# 2008_SablierElectronique_MosfetConnectio.net
KiCad netlist of a schematic drawn in Altium Designer
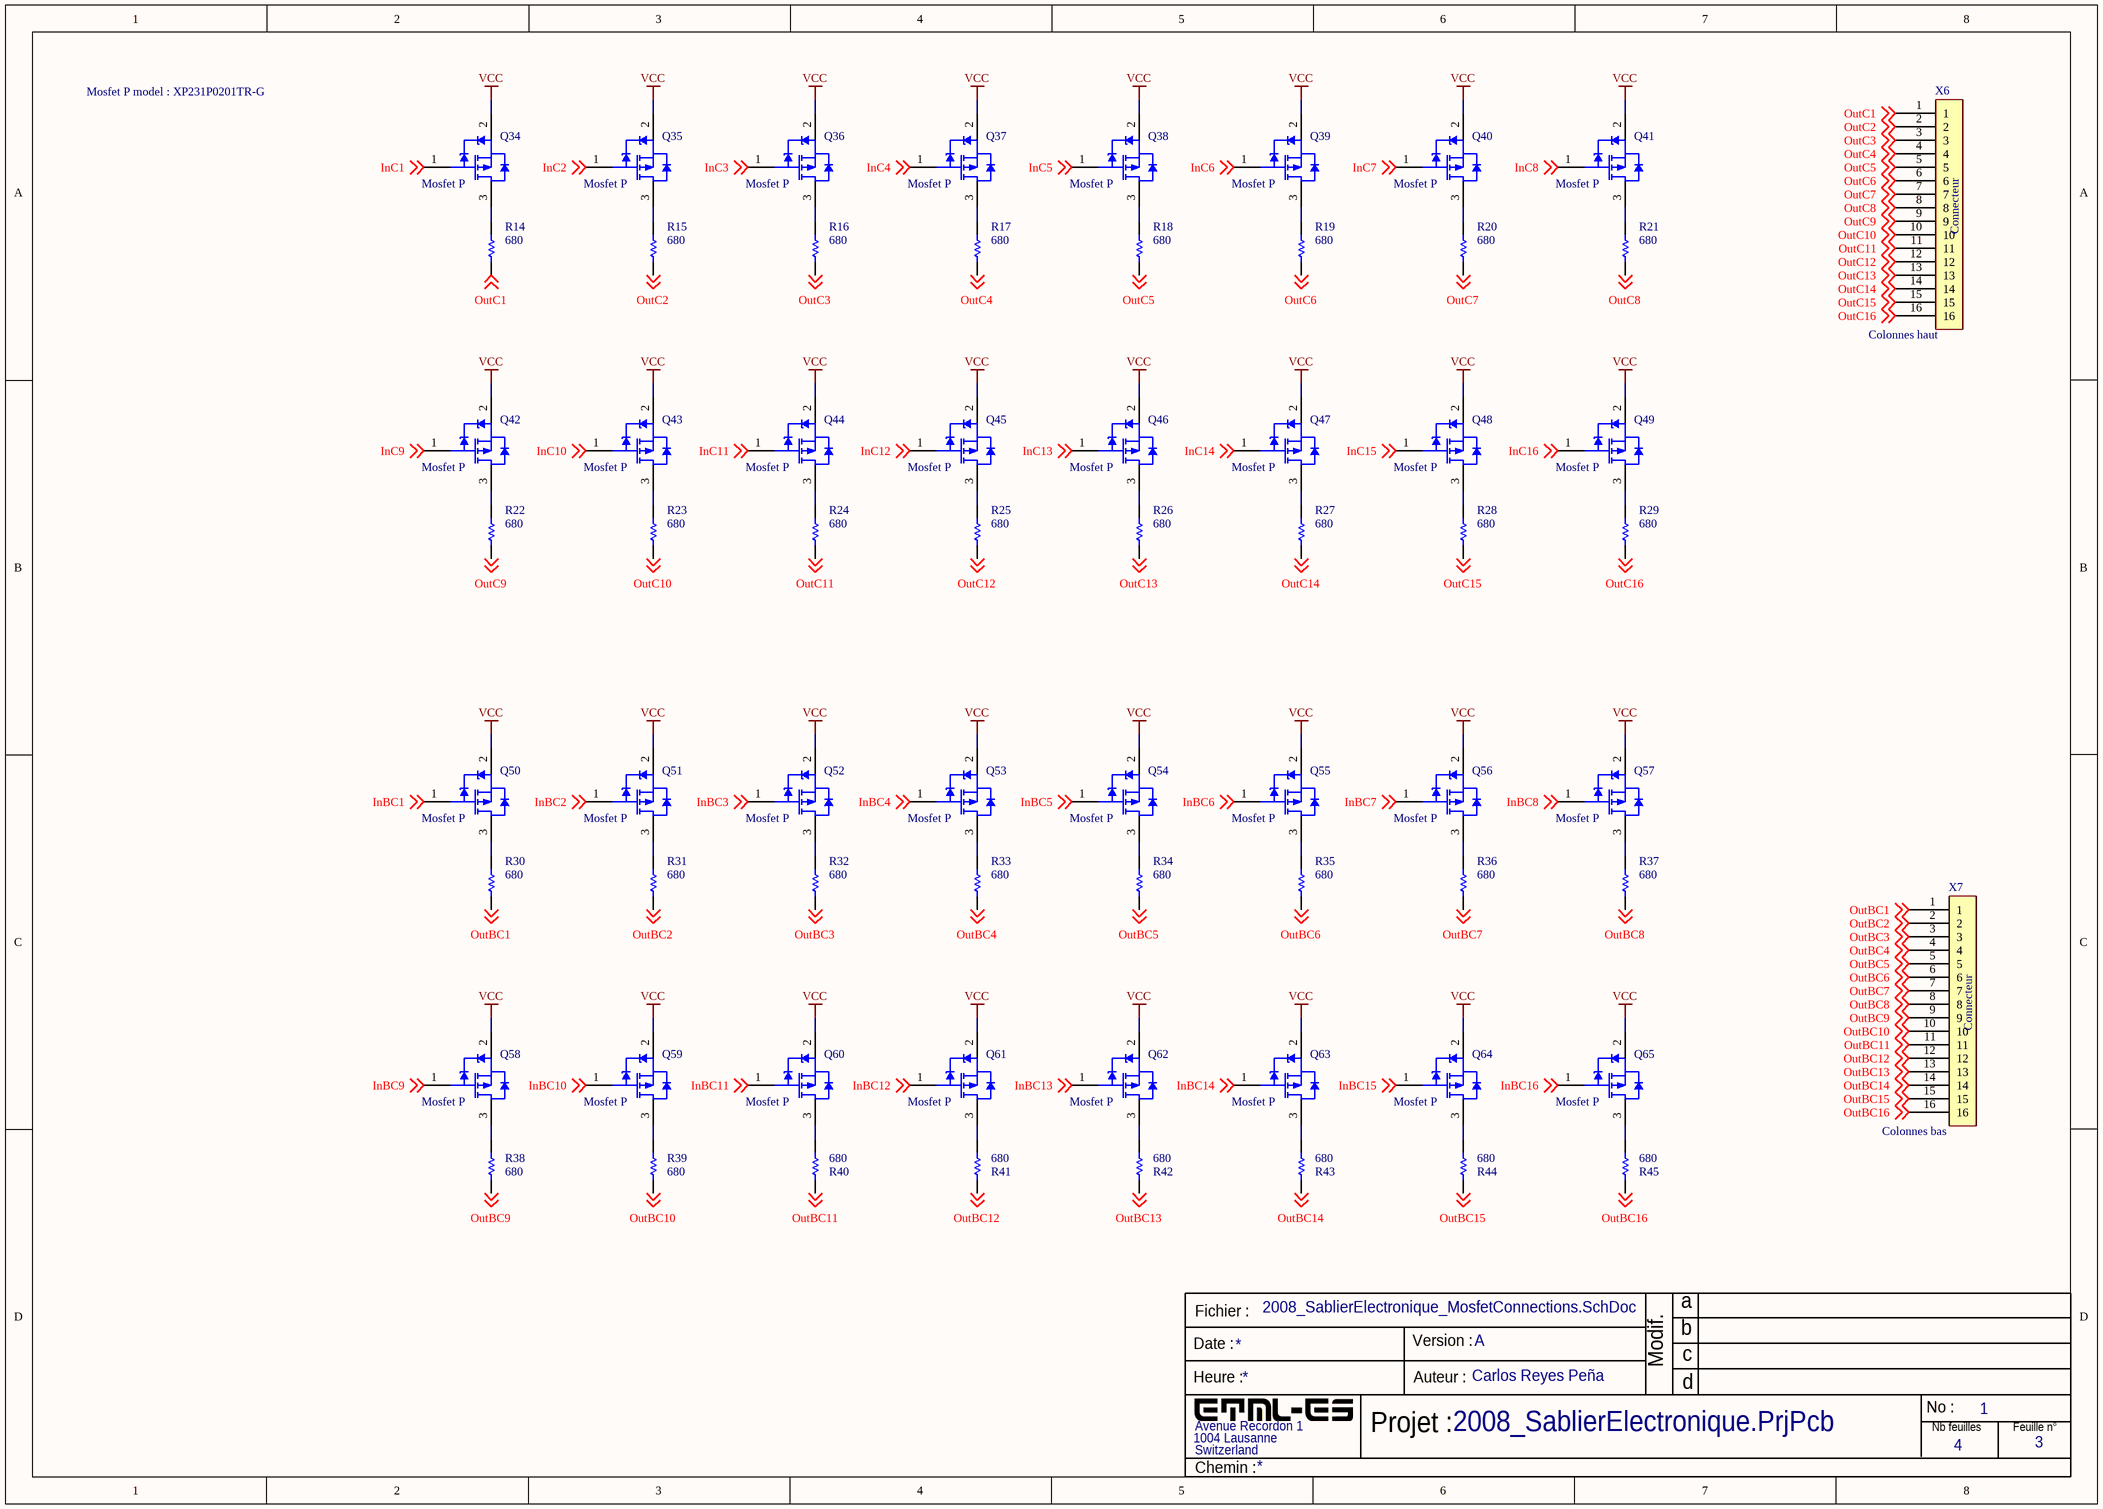
[diagram p0: 2008_SablierElectronique_MosfetConnections.SchDoc]

(export (version "E")
  (design (tool "Eeschema 10.0.6"))
  (components
    (comp (ref "Q34")
      (value "Mosfet P")
      (footprint "FAIR-SOT23-3_V")
      (libsource (lib "2008_SablierElectronique_SCHLIB") (part "Mosfet P"))
    )
    (comp (ref "Q35")
      (value "Mosfet P")
      (footprint "FAIR-SOT23-3_V")
      (libsource (lib "2008_SablierElectronique_SCHLIB") (part "Mosfet P"))
    )
    (comp (ref "Q36")
      (value "Mosfet P")
      (footprint "FAIR-SOT23-3_V")
      (libsource (lib "2008_SablierElectronique_SCHLIB") (part "Mosfet P"))
    )
    (comp (ref "Q37")
      (value "Mosfet P")
      (footprint "FAIR-SOT23-3_V")
      (libsource (lib "2008_SablierElectronique_SCHLIB") (part "Mosfet P"))
    )
    (comp (ref "Q38")
      (value "Mosfet P")
      (footprint "FAIR-SOT23-3_V")
      (libsource (lib "2008_SablierElectronique_SCHLIB") (part "Mosfet P"))
    )
    (comp (ref "Q39")
      (value "Mosfet P")
      (footprint "FAIR-SOT23-3_V")
      (libsource (lib "2008_SablierElectronique_SCHLIB") (part "Mosfet P"))
    )
    (comp (ref "Q40")
      (value "Mosfet P")
      (footprint "FAIR-SOT23-3_V")
      (libsource (lib "2008_SablierElectronique_SCHLIB") (part "Mosfet P"))
    )
    (comp (ref "Q41")
      (value "Mosfet P")
      (footprint "FAIR-SOT23-3_V")
      (libsource (lib "2008_SablierElectronique_SCHLIB") (part "Mosfet P"))
    )
    (comp (ref "Q42")
      (value "Mosfet P")
      (footprint "FAIR-SOT23-3_V")
      (libsource (lib "2008_SablierElectronique_SCHLIB") (part "Mosfet P"))
    )
    (comp (ref "Q43")
      (value "Mosfet P")
      (footprint "FAIR-SOT23-3_V")
      (libsource (lib "2008_SablierElectronique_SCHLIB") (part "Mosfet P"))
    )
    (comp (ref "Q44")
      (value "Mosfet P")
      (footprint "FAIR-SOT23-3_V")
      (libsource (lib "2008_SablierElectronique_SCHLIB") (part "Mosfet P"))
    )
    (comp (ref "Q45")
      (value "Mosfet P")
      (footprint "FAIR-SOT23-3_V")
      (libsource (lib "2008_SablierElectronique_SCHLIB") (part "Mosfet P"))
    )
    (comp (ref "Q46")
      (value "Mosfet P")
      (footprint "FAIR-SOT23-3_V")
      (libsource (lib "2008_SablierElectronique_SCHLIB") (part "Mosfet P"))
    )
    (comp (ref "Q47")
      (value "Mosfet P")
      (footprint "FAIR-SOT23-3_V")
      (libsource (lib "2008_SablierElectronique_SCHLIB") (part "Mosfet P"))
    )
    (comp (ref "Q48")
      (value "Mosfet P")
      (footprint "FAIR-SOT23-3_V")
      (libsource (lib "2008_SablierElectronique_SCHLIB") (part "Mosfet P"))
    )
    (comp (ref "Q49")
      (value "Mosfet P")
      (footprint "FAIR-SOT23-3_V")
      (libsource (lib "2008_SablierElectronique_SCHLIB") (part "Mosfet P"))
    )
    (comp (ref "Q50")
      (value "Mosfet P")
      (footprint "FAIR-SOT23-3_V")
      (libsource (lib "2008_SablierElectronique_SCHLIB") (part "Mosfet P"))
    )
    (comp (ref "Q51")
      (value "Mosfet P")
      (footprint "FAIR-SOT23-3_V")
      (libsource (lib "2008_SablierElectronique_SCHLIB") (part "Mosfet P"))
    )
    (comp (ref "Q52")
      (value "Mosfet P")
      (footprint "FAIR-SOT23-3_V")
      (libsource (lib "2008_SablierElectronique_SCHLIB") (part "Mosfet P"))
    )
    (comp (ref "Q53")
      (value "Mosfet P")
      (footprint "FAIR-SOT23-3_V")
      (libsource (lib "2008_SablierElectronique_SCHLIB") (part "Mosfet P"))
    )
    (comp (ref "Q54")
      (value "Mosfet P")
      (footprint "FAIR-SOT23-3_V")
      (libsource (lib "2008_SablierElectronique_SCHLIB") (part "Mosfet P"))
    )
    (comp (ref "Q55")
      (value "Mosfet P")
      (footprint "FAIR-SOT23-3_V")
      (libsource (lib "2008_SablierElectronique_SCHLIB") (part "Mosfet P"))
    )
    (comp (ref "Q56")
      (value "Mosfet P")
      (footprint "FAIR-SOT23-3_V")
      (libsource (lib "2008_SablierElectronique_SCHLIB") (part "Mosfet P"))
    )
    (comp (ref "Q57")
      (value "Mosfet P")
      (footprint "FAIR-SOT23-3_V")
      (libsource (lib "2008_SablierElectronique_SCHLIB") (part "Mosfet P"))
    )
    (comp (ref "Q58")
      (value "Mosfet P")
      (footprint "FAIR-SOT23-3_V")
      (libsource (lib "2008_SablierElectronique_SCHLIB") (part "Mosfet P"))
    )
    (comp (ref "Q59")
      (value "Mosfet P")
      (footprint "FAIR-SOT23-3_V")
      (libsource (lib "2008_SablierElectronique_SCHLIB") (part "Mosfet P"))
    )
    (comp (ref "Q60")
      (value "Mosfet P")
      (footprint "FAIR-SOT23-3_V")
      (libsource (lib "2008_SablierElectronique_SCHLIB") (part "Mosfet P"))
    )
    (comp (ref "Q61")
      (value "Mosfet P")
      (footprint "FAIR-SOT23-3_V")
      (libsource (lib "2008_SablierElectronique_SCHLIB") (part "Mosfet P"))
    )
    (comp (ref "Q62")
      (value "Mosfet P")
      (footprint "FAIR-SOT23-3_V")
      (libsource (lib "2008_SablierElectronique_SCHLIB") (part "Mosfet P"))
    )
    (comp (ref "Q63")
      (value "Mosfet P")
      (footprint "FAIR-SOT23-3_V")
      (libsource (lib "2008_SablierElectronique_SCHLIB") (part "Mosfet P"))
    )
    (comp (ref "Q64")
      (value "Mosfet P")
      (footprint "FAIR-SOT23-3_V")
      (libsource (lib "2008_SablierElectronique_SCHLIB") (part "Mosfet P"))
    )
    (comp (ref "Q65")
      (value "Mosfet P")
      (footprint "FAIR-SOT23-3_V")
      (libsource (lib "2008_SablierElectronique_SCHLIB") (part "Mosfet P"))
    )
    (comp (ref "R14")
      (value "680")
      (footprint "RESC0805(2012)_L")
      (libsource (lib "2008_SablierElectronique_SCHLIB") (part "RES"))
    )
    (comp (ref "R15")
      (value "680")
      (footprint "RESC0805(2012)_L")
      (libsource (lib "2008_SablierElectronique_SCHLIB") (part "RES"))
    )
    (comp (ref "R16")
      (value "680")
      (footprint "RESC0805(2012)_L")
      (libsource (lib "2008_SablierElectronique_SCHLIB") (part "RES"))
    )
    (comp (ref "R17")
      (value "680")
      (footprint "RESC0805(2012)_L")
      (libsource (lib "2008_SablierElectronique_SCHLIB") (part "RES"))
    )
    (comp (ref "R18")
      (value "680")
      (footprint "RESC0805(2012)_L")
      (libsource (lib "2008_SablierElectronique_SCHLIB") (part "RES"))
    )
    (comp (ref "R19")
      (value "680")
      (footprint "RESC0805(2012)_L")
      (libsource (lib "2008_SablierElectronique_SCHLIB") (part "RES"))
    )
    (comp (ref "R20")
      (value "680")
      (footprint "RESC0805(2012)_L")
      (libsource (lib "2008_SablierElectronique_SCHLIB") (part "RES"))
    )
    (comp (ref "R21")
      (value "680")
      (footprint "RESC0805(2012)_L")
      (libsource (lib "2008_SablierElectronique_SCHLIB") (part "RES"))
    )
    (comp (ref "R22")
      (value "680")
      (footprint "RESC0805(2012)_L")
      (libsource (lib "2008_SablierElectronique_SCHLIB") (part "RES"))
    )
    (comp (ref "R23")
      (value "680")
      (footprint "RESC0805(2012)_L")
      (libsource (lib "2008_SablierElectronique_SCHLIB") (part "RES"))
    )
    (comp (ref "R24")
      (value "680")
      (footprint "RESC0805(2012)_L")
      (libsource (lib "2008_SablierElectronique_SCHLIB") (part "RES"))
    )
    (comp (ref "R25")
      (value "680")
      (footprint "RESC0805(2012)_L")
      (libsource (lib "2008_SablierElectronique_SCHLIB") (part "RES"))
    )
    (comp (ref "R26")
      (value "680")
      (footprint "RESC0805(2012)_L")
      (libsource (lib "2008_SablierElectronique_SCHLIB") (part "RES"))
    )
    (comp (ref "R27")
      (value "680")
      (footprint "RESC0805(2012)_L")
      (libsource (lib "2008_SablierElectronique_SCHLIB") (part "RES"))
    )
    (comp (ref "R28")
      (value "680")
      (footprint "RESC0805(2012)_L")
      (libsource (lib "2008_SablierElectronique_SCHLIB") (part "RES"))
    )
    (comp (ref "R29")
      (value "680")
      (footprint "RESC0805(2012)_L")
      (libsource (lib "2008_SablierElectronique_SCHLIB") (part "RES"))
    )
    (comp (ref "R30")
      (value "680")
      (footprint "RESC0805(2012)_L")
      (libsource (lib "2008_SablierElectronique_SCHLIB") (part "RES"))
    )
    (comp (ref "R31")
      (value "680")
      (footprint "RESC0805(2012)_L")
      (libsource (lib "2008_SablierElectronique_SCHLIB") (part "RES"))
    )
    (comp (ref "R32")
      (value "680")
      (footprint "RESC0805(2012)_L")
      (libsource (lib "2008_SablierElectronique_SCHLIB") (part "RES"))
    )
    (comp (ref "R33")
      (value "680")
      (footprint "RESC0805(2012)_L")
      (libsource (lib "2008_SablierElectronique_SCHLIB") (part "RES"))
    )
    (comp (ref "R34")
      (value "680")
      (footprint "RESC0805(2012)_L")
      (libsource (lib "2008_SablierElectronique_SCHLIB") (part "RES"))
    )
    (comp (ref "R35")
      (value "680")
      (footprint "RESC0805(2012)_L")
      (libsource (lib "2008_SablierElectronique_SCHLIB") (part "RES"))
    )
    (comp (ref "R36")
      (value "680")
      (footprint "RESC0805(2012)_L")
      (libsource (lib "2008_SablierElectronique_SCHLIB") (part "RES"))
    )
    (comp (ref "R37")
      (value "680")
      (footprint "RESC0805(2012)_L")
      (libsource (lib "2008_SablierElectronique_SCHLIB") (part "RES"))
    )
    (comp (ref "R38")
      (value "680")
      (footprint "RESC0805(2012)_L")
      (libsource (lib "2008_SablierElectronique_SCHLIB") (part "RES"))
    )
    (comp (ref "R39")
      (value "680")
      (footprint "RESC0805(2012)_L")
      (libsource (lib "2008_SablierElectronique_SCHLIB") (part "RES"))
    )
    (comp (ref "R40")
      (value "680")
      (footprint "RESC0805(2012)_L")
      (libsource (lib "2008_SablierElectronique_SCHLIB") (part "RES"))
    )
    (comp (ref "R41")
      (value "680")
      (footprint "RESC0805(2012)_L")
      (libsource (lib "2008_SablierElectronique_SCHLIB") (part "RES"))
    )
    (comp (ref "R42")
      (value "680")
      (footprint "RESC0805(2012)_L")
      (libsource (lib "2008_SablierElectronique_SCHLIB") (part "RES"))
    )
    (comp (ref "R43")
      (value "680")
      (footprint "RESC0805(2012)_L")
      (libsource (lib "2008_SablierElectronique_SCHLIB") (part "RES"))
    )
    (comp (ref "R44")
      (value "680")
      (footprint "RESC0805(2012)_L")
      (libsource (lib "2008_SablierElectronique_SCHLIB") (part "RES"))
    )
    (comp (ref "R45")
      (value "680")
      (footprint "RESC0805(2012)_L")
      (libsource (lib "2008_SablierElectronique_SCHLIB") (part "RES"))
    )
    (comp (ref "X6")
      (value "Colonnes haut")
      (footprint "CON8x8(edited)")
      (libsource (lib "2008_SablierElectronique_SCHLIB") (part "Mâle DIN 8 x 8"))
    )
    (comp (ref "X7")
      (value "Colonnes bas")
      (footprint "CON8x8(edited)")
      (libsource (lib "2008_SablierElectronique_SCHLIB") (part "Mâle DIN 8 x 8"))
    )
  )
  (nets
    (net (code "1") (name "InBC1") (class "Default")
      (node (ref "Q50") (pin "1") (pinfunction "G_1") (pintype "passive"))
    )
    (net (code "2") (name "InBC2") (class "Default")
      (node (ref "Q51") (pin "1") (pinfunction "G_1") (pintype "passive"))
    )
    (net (code "3") (name "InBC3") (class "Default")
      (node (ref "Q52") (pin "1") (pinfunction "G_1") (pintype "passive"))
    )
    (net (code "4") (name "InBC4") (class "Default")
      (node (ref "Q53") (pin "1") (pinfunction "G_1") (pintype "passive"))
    )
    (net (code "5") (name "InBC5") (class "Default")
      (node (ref "Q54") (pin "1") (pinfunction "G_1") (pintype "passive"))
    )
    (net (code "6") (name "InBC6") (class "Default")
      (node (ref "Q55") (pin "1") (pinfunction "G_1") (pintype "passive"))
    )
    (net (code "7") (name "InBC7") (class "Default")
      (node (ref "Q56") (pin "1") (pinfunction "G_1") (pintype "passive"))
    )
    (net (code "8") (name "InBC8") (class "Default")
      (node (ref "Q57") (pin "1") (pinfunction "G_1") (pintype "passive"))
    )
    (net (code "9") (name "InBC9") (class "Default")
      (node (ref "Q58") (pin "1") (pinfunction "G_1") (pintype "passive"))
    )
    (net (code "10") (name "InBC10") (class "Default")
      (node (ref "Q59") (pin "1") (pinfunction "G_1") (pintype "passive"))
    )
    (net (code "11") (name "InBC11") (class "Default")
      (node (ref "Q60") (pin "1") (pinfunction "G_1") (pintype "passive"))
    )
    (net (code "12") (name "InBC12") (class "Default")
      (node (ref "Q61") (pin "1") (pinfunction "G_1") (pintype "passive"))
    )
    (net (code "13") (name "InBC13") (class "Default")
      (node (ref "Q62") (pin "1") (pinfunction "G_1") (pintype "passive"))
    )
    (net (code "14") (name "InBC14") (class "Default")
      (node (ref "Q63") (pin "1") (pinfunction "G_1") (pintype "passive"))
    )
    (net (code "15") (name "InBC15") (class "Default")
      (node (ref "Q64") (pin "1") (pinfunction "G_1") (pintype "passive"))
    )
    (net (code "16") (name "InBC16") (class "Default")
      (node (ref "Q65") (pin "1") (pinfunction "G_1") (pintype "passive"))
    )
    (net (code "17") (name "InC1") (class "Default")
      (node (ref "Q34") (pin "1") (pinfunction "G_1") (pintype "passive"))
    )
    (net (code "18") (name "InC2") (class "Default")
      (node (ref "Q35") (pin "1") (pinfunction "G_1") (pintype "passive"))
    )
    (net (code "19") (name "InC3") (class "Default")
      (node (ref "Q36") (pin "1") (pinfunction "G_1") (pintype "passive"))
    )
    (net (code "20") (name "InC4") (class "Default")
      (node (ref "Q37") (pin "1") (pinfunction "G_1") (pintype "passive"))
    )
    (net (code "21") (name "InC5") (class "Default")
      (node (ref "Q38") (pin "1") (pinfunction "G_1") (pintype "passive"))
    )
    (net (code "22") (name "InC6") (class "Default")
      (node (ref "Q39") (pin "1") (pinfunction "G_1") (pintype "passive"))
    )
    (net (code "23") (name "InC7") (class "Default")
      (node (ref "Q40") (pin "1") (pinfunction "G_1") (pintype "passive"))
    )
    (net (code "24") (name "InC8") (class "Default")
      (node (ref "Q41") (pin "1") (pinfunction "G_1") (pintype "passive"))
    )
    (net (code "25") (name "InC9") (class "Default")
      (node (ref "Q42") (pin "1") (pinfunction "G_1") (pintype "passive"))
    )
    (net (code "26") (name "InC10") (class "Default")
      (node (ref "Q43") (pin "1") (pinfunction "G_1") (pintype "passive"))
    )
    (net (code "27") (name "InC11") (class "Default")
      (node (ref "Q44") (pin "1") (pinfunction "G_1") (pintype "passive"))
    )
    (net (code "28") (name "InC12") (class "Default")
      (node (ref "Q45") (pin "1") (pinfunction "G_1") (pintype "passive"))
    )
    (net (code "29") (name "InC13") (class "Default")
      (node (ref "Q46") (pin "1") (pinfunction "G_1") (pintype "passive"))
    )
    (net (code "30") (name "InC14") (class "Default")
      (node (ref "Q47") (pin "1") (pinfunction "G_1") (pintype "passive"))
    )
    (net (code "31") (name "InC15") (class "Default")
      (node (ref "Q48") (pin "1") (pinfunction "G_1") (pintype "passive"))
    )
    (net (code "32") (name "InC16") (class "Default")
      (node (ref "Q49") (pin "1") (pinfunction "G_1") (pintype "passive"))
    )
    (net (code "33") (name "Net-(Q34-D)") (class "Default")
      (node (ref "Q34") (pin "3") (pinfunction "D_3") (pintype "passive"))
      (node (ref "R14") (pin "2") (pinfunction "2_2") (pintype "passive"))
    )
    (net (code "34") (name "Net-(Q35-D)") (class "Default")
      (node (ref "Q35") (pin "3") (pinfunction "D_3") (pintype "passive"))
      (node (ref "R15") (pin "2") (pinfunction "2_2") (pintype "passive"))
    )
    (net (code "35") (name "Net-(Q36-D)") (class "Default")
      (node (ref "Q36") (pin "3") (pinfunction "D_3") (pintype "passive"))
      (node (ref "R16") (pin "2") (pinfunction "2_2") (pintype "passive"))
    )
    (net (code "36") (name "Net-(Q37-D)") (class "Default")
      (node (ref "Q37") (pin "3") (pinfunction "D_3") (pintype "passive"))
      (node (ref "R17") (pin "2") (pinfunction "2_2") (pintype "passive"))
    )
    (net (code "37") (name "Net-(Q38-D)") (class "Default")
      (node (ref "Q38") (pin "3") (pinfunction "D_3") (pintype "passive"))
      (node (ref "R18") (pin "2") (pinfunction "2_2") (pintype "passive"))
    )
    (net (code "38") (name "Net-(Q39-D)") (class "Default")
      (node (ref "Q39") (pin "3") (pinfunction "D_3") (pintype "passive"))
      (node (ref "R19") (pin "2") (pinfunction "2_2") (pintype "passive"))
    )
    (net (code "39") (name "Net-(Q40-D)") (class "Default")
      (node (ref "Q40") (pin "3") (pinfunction "D_3") (pintype "passive"))
      (node (ref "R20") (pin "2") (pinfunction "2_2") (pintype "passive"))
    )
    (net (code "40") (name "Net-(Q41-D)") (class "Default")
      (node (ref "Q41") (pin "3") (pinfunction "D_3") (pintype "passive"))
      (node (ref "R21") (pin "2") (pinfunction "2_2") (pintype "passive"))
    )
    (net (code "41") (name "Net-(Q42-D)") (class "Default")
      (node (ref "Q42") (pin "3") (pinfunction "D_3") (pintype "passive"))
      (node (ref "R22") (pin "2") (pinfunction "2_2") (pintype "passive"))
    )
    (net (code "42") (name "Net-(Q43-D)") (class "Default")
      (node (ref "Q43") (pin "3") (pinfunction "D_3") (pintype "passive"))
      (node (ref "R23") (pin "2") (pinfunction "2_2") (pintype "passive"))
    )
    (net (code "43") (name "Net-(Q44-D)") (class "Default")
      (node (ref "Q44") (pin "3") (pinfunction "D_3") (pintype "passive"))
      (node (ref "R24") (pin "2") (pinfunction "2_2") (pintype "passive"))
    )
    (net (code "44") (name "Net-(Q45-D)") (class "Default")
      (node (ref "Q45") (pin "3") (pinfunction "D_3") (pintype "passive"))
      (node (ref "R25") (pin "2") (pinfunction "2_2") (pintype "passive"))
    )
    (net (code "45") (name "Net-(Q46-D)") (class "Default")
      (node (ref "Q46") (pin "3") (pinfunction "D_3") (pintype "passive"))
      (node (ref "R26") (pin "2") (pinfunction "2_2") (pintype "passive"))
    )
    (net (code "46") (name "Net-(Q47-D)") (class "Default")
      (node (ref "Q47") (pin "3") (pinfunction "D_3") (pintype "passive"))
      (node (ref "R27") (pin "2") (pinfunction "2_2") (pintype "passive"))
    )
    (net (code "47") (name "Net-(Q48-D)") (class "Default")
      (node (ref "Q48") (pin "3") (pinfunction "D_3") (pintype "passive"))
      (node (ref "R28") (pin "2") (pinfunction "2_2") (pintype "passive"))
    )
    (net (code "48") (name "Net-(Q49-D)") (class "Default")
      (node (ref "Q49") (pin "3") (pinfunction "D_3") (pintype "passive"))
      (node (ref "R29") (pin "2") (pinfunction "2_2") (pintype "passive"))
    )
    (net (code "49") (name "Net-(Q50-D)") (class "Default")
      (node (ref "Q50") (pin "3") (pinfunction "D_3") (pintype "passive"))
      (node (ref "R30") (pin "2") (pinfunction "2_2") (pintype "passive"))
    )
    (net (code "50") (name "Net-(Q51-D)") (class "Default")
      (node (ref "Q51") (pin "3") (pinfunction "D_3") (pintype "passive"))
      (node (ref "R31") (pin "2") (pinfunction "2_2") (pintype "passive"))
    )
    (net (code "51") (name "Net-(Q52-D)") (class "Default")
      (node (ref "Q52") (pin "3") (pinfunction "D_3") (pintype "passive"))
      (node (ref "R32") (pin "2") (pinfunction "2_2") (pintype "passive"))
    )
    (net (code "52") (name "Net-(Q53-D)") (class "Default")
      (node (ref "Q53") (pin "3") (pinfunction "D_3") (pintype "passive"))
      (node (ref "R33") (pin "2") (pinfunction "2_2") (pintype "passive"))
    )
    (net (code "53") (name "Net-(Q54-D)") (class "Default")
      (node (ref "Q54") (pin "3") (pinfunction "D_3") (pintype "passive"))
      (node (ref "R34") (pin "2") (pinfunction "2_2") (pintype "passive"))
    )
    (net (code "54") (name "Net-(Q55-D)") (class "Default")
      (node (ref "Q55") (pin "3") (pinfunction "D_3") (pintype "passive"))
      (node (ref "R35") (pin "2") (pinfunction "2_2") (pintype "passive"))
    )
    (net (code "55") (name "Net-(Q56-D)") (class "Default")
      (node (ref "Q56") (pin "3") (pinfunction "D_3") (pintype "passive"))
      (node (ref "R36") (pin "2") (pinfunction "2_2") (pintype "passive"))
    )
    (net (code "56") (name "Net-(Q57-D)") (class "Default")
      (node (ref "Q57") (pin "3") (pinfunction "D_3") (pintype "passive"))
      (node (ref "R37") (pin "2") (pinfunction "2_2") (pintype "passive"))
    )
    (net (code "57") (name "Net-(Q58-D)") (class "Default")
      (node (ref "Q58") (pin "3") (pinfunction "D_3") (pintype "passive"))
      (node (ref "R38") (pin "2") (pinfunction "2_2") (pintype "passive"))
    )
    (net (code "58") (name "Net-(Q59-D)") (class "Default")
      (node (ref "Q59") (pin "3") (pinfunction "D_3") (pintype "passive"))
      (node (ref "R39") (pin "2") (pinfunction "2_2") (pintype "passive"))
    )
    (net (code "59") (name "Net-(Q60-D)") (class "Default")
      (node (ref "Q60") (pin "3") (pinfunction "D_3") (pintype "passive"))
      (node (ref "R40") (pin "2") (pinfunction "2_2") (pintype "passive"))
    )
    (net (code "60") (name "Net-(Q61-D)") (class "Default")
      (node (ref "Q61") (pin "3") (pinfunction "D_3") (pintype "passive"))
      (node (ref "R41") (pin "2") (pinfunction "2_2") (pintype "passive"))
    )
    (net (code "61") (name "Net-(Q62-D)") (class "Default")
      (node (ref "Q62") (pin "3") (pinfunction "D_3") (pintype "passive"))
      (node (ref "R42") (pin "2") (pinfunction "2_2") (pintype "passive"))
    )
    (net (code "62") (name "Net-(Q63-D)") (class "Default")
      (node (ref "Q63") (pin "3") (pinfunction "D_3") (pintype "passive"))
      (node (ref "R43") (pin "2") (pinfunction "2_2") (pintype "passive"))
    )
    (net (code "63") (name "Net-(Q64-D)") (class "Default")
      (node (ref "Q64") (pin "3") (pinfunction "D_3") (pintype "passive"))
      (node (ref "R44") (pin "2") (pinfunction "2_2") (pintype "passive"))
    )
    (net (code "64") (name "Net-(Q65-D)") (class "Default")
      (node (ref "Q65") (pin "3") (pinfunction "D_3") (pintype "passive"))
      (node (ref "R45") (pin "2") (pinfunction "2_2") (pintype "passive"))
    )
    (net (code "65") (name "OutBC1") (class "Default")
      (node (ref "R30") (pin "1") (pinfunction "1_1") (pintype "passive"))
      (node (ref "X7") (pin "1") (pinfunction "1_1") (pintype "passive"))
    )
    (net (code "66") (name "OutBC2") (class "Default")
      (node (ref "R31") (pin "1") (pinfunction "1_1") (pintype "passive"))
      (node (ref "X7") (pin "2") (pinfunction "2_2") (pintype "passive"))
    )
    (net (code "67") (name "OutBC3") (class "Default")
      (node (ref "R32") (pin "1") (pinfunction "1_1") (pintype "passive"))
      (node (ref "X7") (pin "3") (pinfunction "3_3") (pintype "passive"))
    )
    (net (code "68") (name "OutBC4") (class "Default")
      (node (ref "R33") (pin "1") (pinfunction "1_1") (pintype "passive"))
      (node (ref "X7") (pin "4") (pinfunction "4_4") (pintype "passive"))
    )
    (net (code "69") (name "OutBC5") (class "Default")
      (node (ref "R34") (pin "1") (pinfunction "1_1") (pintype "passive"))
      (node (ref "X7") (pin "5") (pinfunction "5_5") (pintype "passive"))
    )
    (net (code "70") (name "OutBC6") (class "Default")
      (node (ref "R35") (pin "1") (pinfunction "1_1") (pintype "passive"))
      (node (ref "X7") (pin "6") (pinfunction "6_6") (pintype "passive"))
    )
    (net (code "71") (name "OutBC7") (class "Default")
      (node (ref "R36") (pin "1") (pinfunction "1_1") (pintype "passive"))
      (node (ref "X7") (pin "7") (pinfunction "7_7") (pintype "passive"))
    )
    (net (code "72") (name "OutBC8") (class "Default")
      (node (ref "R37") (pin "1") (pinfunction "1_1") (pintype "passive"))
      (node (ref "X7") (pin "8") (pinfunction "8_8") (pintype "passive"))
    )
    (net (code "73") (name "OutBC9") (class "Default")
      (node (ref "R38") (pin "1") (pinfunction "1_1") (pintype "passive"))
      (node (ref "X7") (pin "9") (pinfunction "9_9") (pintype "passive"))
    )
    (net (code "74") (name "OutBC10") (class "Default")
      (node (ref "R39") (pin "1") (pinfunction "1_1") (pintype "passive"))
      (node (ref "X7") (pin "10") (pinfunction "10_10") (pintype "passive"))
    )
    (net (code "75") (name "OutBC11") (class "Default")
      (node (ref "R40") (pin "1") (pinfunction "1_1") (pintype "passive"))
      (node (ref "X7") (pin "11") (pinfunction "11_11") (pintype "passive"))
    )
    (net (code "76") (name "OutBC12") (class "Default")
      (node (ref "R41") (pin "1") (pinfunction "1_1") (pintype "passive"))
      (node (ref "X7") (pin "12") (pinfunction "12_12") (pintype "passive"))
    )
    (net (code "77") (name "OutBC13") (class "Default")
      (node (ref "R42") (pin "1") (pinfunction "1_1") (pintype "passive"))
      (node (ref "X7") (pin "13") (pinfunction "13_13") (pintype "passive"))
    )
    (net (code "78") (name "OutBC14") (class "Default")
      (node (ref "R43") (pin "1") (pinfunction "1_1") (pintype "passive"))
      (node (ref "X7") (pin "14") (pinfunction "14_14") (pintype "passive"))
    )
    (net (code "79") (name "OutBC15") (class "Default")
      (node (ref "R44") (pin "1") (pinfunction "1_1") (pintype "passive"))
      (node (ref "X7") (pin "15") (pinfunction "15_15") (pintype "passive"))
    )
    (net (code "80") (name "OutBC16") (class "Default")
      (node (ref "R45") (pin "1") (pinfunction "1_1") (pintype "passive"))
      (node (ref "X7") (pin "16") (pinfunction "16_16") (pintype "passive"))
    )
    (net (code "81") (name "OutC1") (class "Default")
      (node (ref "R14") (pin "1") (pinfunction "1_1") (pintype "passive"))
      (node (ref "X6") (pin "1") (pinfunction "1_1") (pintype "passive"))
    )
    (net (code "82") (name "OutC2") (class "Default")
      (node (ref "R15") (pin "1") (pinfunction "1_1") (pintype "passive"))
      (node (ref "X6") (pin "2") (pinfunction "2_2") (pintype "passive"))
    )
    (net (code "83") (name "OutC3") (class "Default")
      (node (ref "R16") (pin "1") (pinfunction "1_1") (pintype "passive"))
      (node (ref "X6") (pin "3") (pinfunction "3_3") (pintype "passive"))
    )
    (net (code "84") (name "OutC4") (class "Default")
      (node (ref "R17") (pin "1") (pinfunction "1_1") (pintype "passive"))
      (node (ref "X6") (pin "4") (pinfunction "4_4") (pintype "passive"))
    )
    (net (code "85") (name "OutC5") (class "Default")
      (node (ref "R18") (pin "1") (pinfunction "1_1") (pintype "passive"))
      (node (ref "X6") (pin "5") (pinfunction "5_5") (pintype "passive"))
    )
    (net (code "86") (name "OutC6") (class "Default")
      (node (ref "R19") (pin "1") (pinfunction "1_1") (pintype "passive"))
      (node (ref "X6") (pin "6") (pinfunction "6_6") (pintype "passive"))
    )
    (net (code "87") (name "OutC7") (class "Default")
      (node (ref "R20") (pin "1") (pinfunction "1_1") (pintype "passive"))
      (node (ref "X6") (pin "7") (pinfunction "7_7") (pintype "passive"))
    )
    (net (code "88") (name "OutC8") (class "Default")
      (node (ref "R21") (pin "1") (pinfunction "1_1") (pintype "passive"))
      (node (ref "X6") (pin "8") (pinfunction "8_8") (pintype "passive"))
    )
    (net (code "89") (name "OutC9") (class "Default")
      (node (ref "R22") (pin "1") (pinfunction "1_1") (pintype "passive"))
      (node (ref "X6") (pin "9") (pinfunction "9_9") (pintype "passive"))
    )
    (net (code "90") (name "OutC10") (class "Default")
      (node (ref "R23") (pin "1") (pinfunction "1_1") (pintype "passive"))
      (node (ref "X6") (pin "10") (pinfunction "10_10") (pintype "passive"))
    )
    (net (code "91") (name "OutC11") (class "Default")
      (node (ref "R24") (pin "1") (pinfunction "1_1") (pintype "passive"))
      (node (ref "X6") (pin "11") (pinfunction "11_11") (pintype "passive"))
    )
    (net (code "92") (name "OutC12") (class "Default")
      (node (ref "R25") (pin "1") (pinfunction "1_1") (pintype "passive"))
      (node (ref "X6") (pin "12") (pinfunction "12_12") (pintype "passive"))
    )
    (net (code "93") (name "OutC13") (class "Default")
      (node (ref "R26") (pin "1") (pinfunction "1_1") (pintype "passive"))
      (node (ref "X6") (pin "13") (pinfunction "13_13") (pintype "passive"))
    )
    (net (code "94") (name "OutC14") (class "Default")
      (node (ref "R27") (pin "1") (pinfunction "1_1") (pintype "passive"))
      (node (ref "X6") (pin "14") (pinfunction "14_14") (pintype "passive"))
    )
    (net (code "95") (name "OutC15") (class "Default")
      (node (ref "R28") (pin "1") (pinfunction "1_1") (pintype "passive"))
      (node (ref "X6") (pin "15") (pinfunction "15_15") (pintype "passive"))
    )
    (net (code "96") (name "OutC16") (class "Default")
      (node (ref "R29") (pin "1") (pinfunction "1_1") (pintype "passive"))
      (node (ref "X6") (pin "16") (pinfunction "16_16") (pintype "passive"))
    )
    (net (code "97") (name "VCC") (class "Default")
      (node (ref "Q34") (pin "2") (pinfunction "S_2") (pintype "passive"))
      (node (ref "Q35") (pin "2") (pinfunction "S_2") (pintype "passive"))
      (node (ref "Q36") (pin "2") (pinfunction "S_2") (pintype "passive"))
      (node (ref "Q37") (pin "2") (pinfunction "S_2") (pintype "passive"))
      (node (ref "Q38") (pin "2") (pinfunction "S_2") (pintype "passive"))
      (node (ref "Q39") (pin "2") (pinfunction "S_2") (pintype "passive"))
      (node (ref "Q40") (pin "2") (pinfunction "S_2") (pintype "passive"))
      (node (ref "Q41") (pin "2") (pinfunction "S_2") (pintype "passive"))
      (node (ref "Q42") (pin "2") (pinfunction "S_2") (pintype "passive"))
      (node (ref "Q43") (pin "2") (pinfunction "S_2") (pintype "passive"))
      (node (ref "Q44") (pin "2") (pinfunction "S_2") (pintype "passive"))
      (node (ref "Q45") (pin "2") (pinfunction "S_2") (pintype "passive"))
      (node (ref "Q46") (pin "2") (pinfunction "S_2") (pintype "passive"))
      (node (ref "Q47") (pin "2") (pinfunction "S_2") (pintype "passive"))
      (node (ref "Q48") (pin "2") (pinfunction "S_2") (pintype "passive"))
      (node (ref "Q49") (pin "2") (pinfunction "S_2") (pintype "passive"))
      (node (ref "Q50") (pin "2") (pinfunction "S_2") (pintype "passive"))
      (node (ref "Q51") (pin "2") (pinfunction "S_2") (pintype "passive"))
      (node (ref "Q52") (pin "2") (pinfunction "S_2") (pintype "passive"))
      (node (ref "Q53") (pin "2") (pinfunction "S_2") (pintype "passive"))
      (node (ref "Q54") (pin "2") (pinfunction "S_2") (pintype "passive"))
      (node (ref "Q55") (pin "2") (pinfunction "S_2") (pintype "passive"))
      (node (ref "Q56") (pin "2") (pinfunction "S_2") (pintype "passive"))
      (node (ref "Q57") (pin "2") (pinfunction "S_2") (pintype "passive"))
      (node (ref "Q58") (pin "2") (pinfunction "S_2") (pintype "passive"))
      (node (ref "Q59") (pin "2") (pinfunction "S_2") (pintype "passive"))
      (node (ref "Q60") (pin "2") (pinfunction "S_2") (pintype "passive"))
      (node (ref "Q61") (pin "2") (pinfunction "S_2") (pintype "passive"))
      (node (ref "Q62") (pin "2") (pinfunction "S_2") (pintype "passive"))
      (node (ref "Q63") (pin "2") (pinfunction "S_2") (pintype "passive"))
      (node (ref "Q64") (pin "2") (pinfunction "S_2") (pintype "passive"))
      (node (ref "Q65") (pin "2") (pinfunction "S_2") (pintype "passive"))
    )
  )
)
